# RPi_Motor_Driver_Rev_0_2.net
KiCad netlist of a schematic drawn in Altium Designer
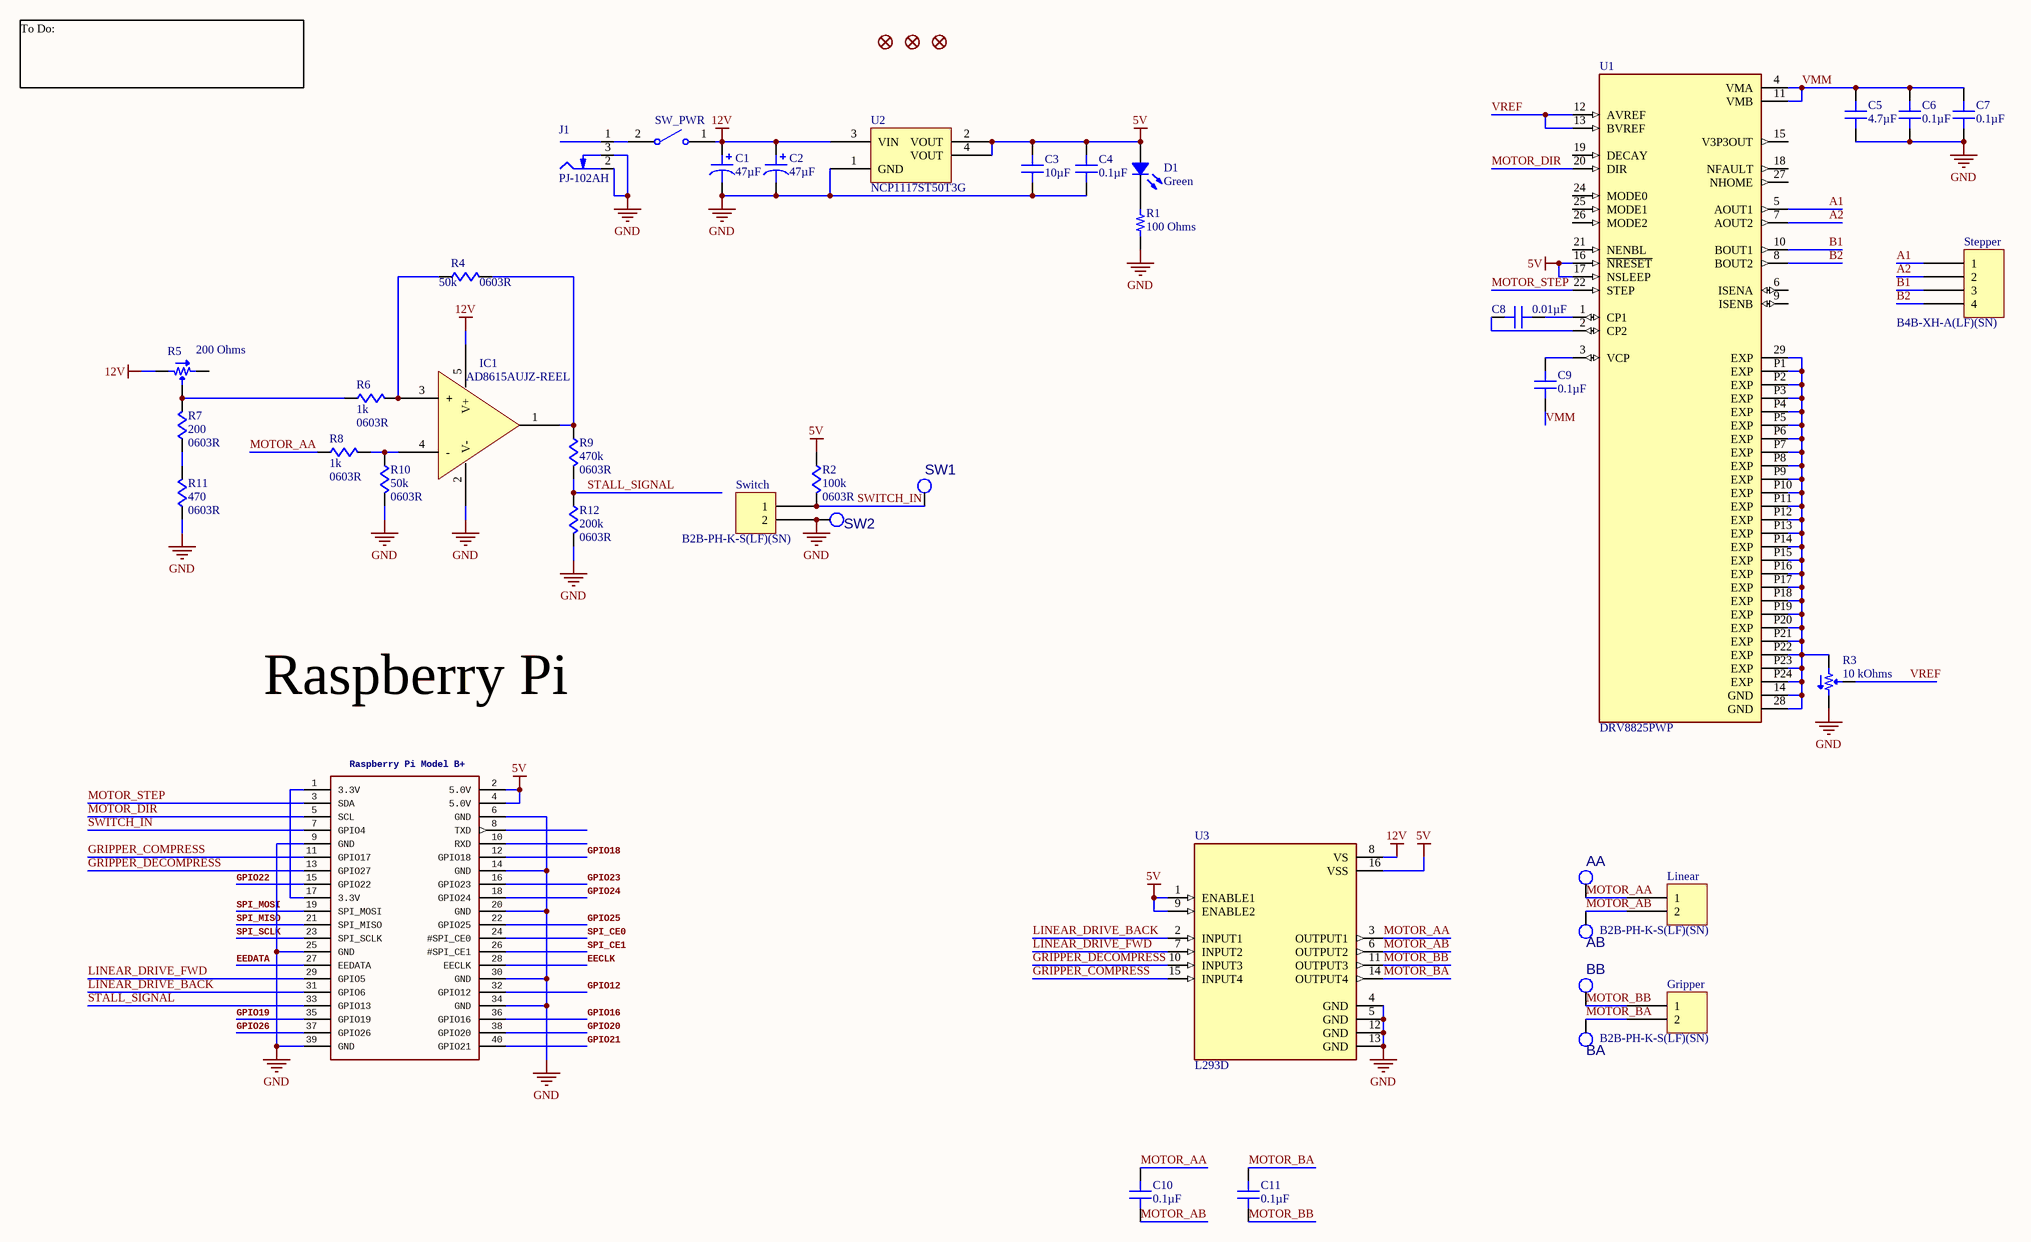
[diagram p0: RPi Motor Driver Rev 0.2.SchDoc]

(export (version "E")
  (design (tool "Eeschema 10.0.6"))
  (components
    (comp (ref "AA")
      (value "TH_Testpoint_40mil")
      (footprint "TH_Testpoint_40mil")
      (description "TH Testpoint")
      (libsource (lib "Testpoint") (part "TH_Testpoint_40mil"))
    )
    (comp (ref "AB")
      (value "TH_Testpoint_40mil")
      (footprint "TH_Testpoint_40mil")
      (description "TH Testpoint")
      (libsource (lib "Testpoint") (part "TH_Testpoint_40mil"))
    )
    (comp (ref "BA")
      (value "TH_Testpoint_40mil")
      (footprint "TH_Testpoint_40mil")
      (description "TH Testpoint")
      (libsource (lib "Testpoint") (part "TH_Testpoint_40mil"))
    )
    (comp (ref "BB")
      (value "TH_Testpoint_40mil")
      (footprint "TH_Testpoint_40mil")
      (description "TH Testpoint")
      (libsource (lib "Testpoint") (part "TH_Testpoint_40mil"))
    )
    (comp (ref "C1")
      (value "47µF")
      (footprint "CAP ALSMD 6.6MM H6.1MM")
      (description "CAP ALUM 47UF 20% 35V SMD")
      (fields (field (name "PART NUMBER") "EEE-FP1V470AP") (field (name "MANUFACTURER") "Nichicon"))
      (libsource (lib "Celestial Altium Library - altium_library") (part "Polarised Capacitor"))
    )
    (comp (ref "C2")
      (value "47µF")
      (footprint "CAP ALSMD 6.6MM H6.1MM")
      (description "CAP ALUM 47UF 20% 35V SMD")
      (fields (field (name "PART NUMBER") "EEE-FP1V470AP") (field (name "MANUFACTURER") "Nichicon"))
      (libsource (lib "Celestial Altium Library - altium_library") (part "Polarised Capacitor"))
    )
    (comp (ref "C3")
      (value "10µF")
      (footprint "CAP 0805_2012")
      (description "CAP CER 10UF 25V X5R 0805")
      (fields
        (field (name "PART NUMBER") "C2012X5R1E106K085AC")
        (field (name "MANUFACTURER") "TDK Corporation")
      )
      (libsource (lib "Celestial Altium Library - altium_library") (part "Capacitor"))
    )
    (comp (ref "C4")
      (value "0.1µF")
      (footprint "CAP 0603_1608")
      (description "CAP CER 0.1UF 50V X7R 0603")
      (fields
        (field (name "PART NUMBER") "CGA3E2X7R1H104K080AE")
        (field (name "MANUFACTURER") "TDK Corporation")
      )
      (libsource (lib "Celestial Altium Library - altium_library") (part "Capacitor"))
    )
    (comp (ref "C5")
      (value "4.7µF")
      (footprint "CAP 0603_1608")
      (description "CAP CER 4.7UF 35V X5R 0603")
      (fields
        (field (name "PART NUMBER") "C1608X5R1V475M080AC")
        (field (name "MANUFACTURER") "TDK Corporation")
      )
      (libsource (lib "Celestial Altium Library - altium_library") (part "Capacitor"))
    )
    (comp (ref "C6")
      (value "0.1µF")
      (footprint "CAP 0603_1608")
      (description "CAP CER 0.1UF 50V X7R 0603")
      (fields
        (field (name "PART NUMBER") "CGA3E2X7R1H104K080AE")
        (field (name "MANUFACTURER") "TDK Corporation")
      )
      (libsource (lib "Celestial Altium Library - altium_library") (part "Capacitor"))
    )
    (comp (ref "C7")
      (value "0.1µF")
      (footprint "CAP 0603_1608")
      (description "CAP CER 0.1UF 50V X7R 0603")
      (fields
        (field (name "PART NUMBER") "CGA3E2X7R1H104K080AE")
        (field (name "MANUFACTURER") "TDK Corporation")
      )
      (libsource (lib "Celestial Altium Library - altium_library") (part "Capacitor"))
    )
    (comp (ref "C8")
      (value "0.01µF")
      (footprint "CAP 0603_1608")
      (description "CAP CER 0.01UF 250V X7R 0603")
      (fields (field (name "PART NUMBER") "C0603C103KARACAUTO") (field (name "MANUFACTURER") "KEMET"))
      (libsource (lib "Celestial Altium Library - altium_library") (part "Capacitor"))
    )
    (comp (ref "C9")
      (value "0.1µF")
      (footprint "CAP 0603_1608")
      (description "CAP CER 0.1UF 50V X7R 0603")
      (fields
        (field (name "PART NUMBER") "CGA3E2X7R1H104K080AE")
        (field (name "MANUFACTURER") "TDK Corporation")
      )
      (libsource (lib "Celestial Altium Library - altium_library") (part "Capacitor"))
    )
    (comp (ref "C10")
      (value "0.1µF")
      (footprint "CAP 0603_1608")
      (description "CAP CER 0.1UF 50V X7R 0603")
      (fields
        (field (name "PART NUMBER") "CGA3E2X7R1H104K080AE")
        (field (name "MANUFACTURER") "TDK Corporation")
      )
      (libsource (lib "Celestial Altium Library - altium_library") (part "Capacitor"))
    )
    (comp (ref "C11")
      (value "0.1µF")
      (footprint "CAP 0603_1608")
      (description "CAP CER 0.1UF 50V X7R 0603")
      (fields
        (field (name "PART NUMBER") "CGA3E2X7R1H104K080AE")
        (field (name "MANUFACTURER") "TDK Corporation")
      )
      (libsource (lib "Celestial Altium Library - altium_library") (part "Capacitor"))
    )
    (comp (ref "D1")
      (value "Green")
      (footprint "LED 0603_1608 GREEN")
      (description "LED GREEN CLEAR 1608 SMD")
      (fields (field (name "PART NUMBER") "APT1608CGCK") (field (name "MANUFACTURER") "Kingbright"))
      (libsource (lib "Celestial Altium Library - altium_library") (part "LED"))
    )
    (comp (ref "FID1")
      (value "FIDUCIAL\"\"")
      (footprint "FIDUCIAL_1MM")
      (description "Fiducial Alignment PointsVarious fiducial points for machine vision alignment.")
      (libsource (lib "microbuilder") (part "FIDUCIAL{dblquote}{dblquote}"))
    )
    (comp (ref "FID2")
      (value "FIDUCIAL\"\"")
      (footprint "FIDUCIAL_1MM")
      (description "Fiducial Alignment PointsVarious fiducial points for machine vision alignment.")
      (libsource (lib "microbuilder") (part "FIDUCIAL{dblquote}{dblquote}"))
    )
    (comp (ref "FID3")
      (value "FIDUCIAL\"\"")
      (footprint "FIDUCIAL_1MM")
      (description "Fiducial Alignment PointsVarious fiducial points for machine vision alignment.")
      (libsource (lib "microbuilder") (part "FIDUCIAL{dblquote}{dblquote}"))
    )
    (comp (ref "Gripper")
      (value "B2B-PH-K-S(LF)(SN)")
      (footprint "JST B2B-PH-K")
      (description "CONN HEADER VERT 2POS 2MM")
      (fields (field (name "MANUFACTURER") "JST Sales America Inc."))
      (libsource (lib "") (part "2 Pin_1"))
    )
    (comp (ref "IC1")
      (value "AD8615AUJZ-REEL")
      (footprint "ANALOG TSOT-23-5 UJ-5")
      (description "IC OPAMP GP 1 CIRCUIT TSOT23-5")
      (fields (field (name "MANUFACTURER") "Analog Devices Inc."))
      (libsource (lib "Celestial Altium Library - altium_library") (part "ANALOG DEV AD8615AUJZ"))
    )
    (comp (ref "J1")
      (value "PJ-102AH")
      (footprint "CUI PJ-102AH")
      (description "CONN PWR JACK 2X5.5MM SOLDER")
      (fields (field (name "MANUFACTURER") "CUI Devices"))
      (libsource (lib "Celestial Altium Library - altium_library") (part "Barrel Connector"))
    )
    (comp (ref "Linear")
      (value "B2B-PH-K-S(LF)(SN)")
      (footprint "JST B2B-PH-K")
      (description "CONN HEADER VERT 2POS 2MM")
      (fields (field (name "MANUFACTURER") "JST Sales America Inc."))
      (libsource (lib "") (part "2 Pin_1"))
    )
    (comp (ref "R1")
      (value "100 Ohms")
      (footprint "RES 0603_1608")
      (description "RES 100 OHM 0.1% 1/16W 0603")
      (fields
        (field (name "PART NUMBER") "RNCS0603BKE100R")
        (field (name "MANUFACTURER") "Stackpole Electronics Inc")
      )
      (libsource (lib "Celestial Altium Library - altium_library") (part "Resistor"))
    )
    (comp (ref "R2")
      (value "100k")
      (footprint "0603R")
      (fields (field (name "Comment") "Resistor 0603"))
      (libsource (lib "MikesAltiumLibrary") (part "Resistor"))
    )
    (comp (ref "R3")
      (value "10 kOhms")
      (footprint "POT BOURNS TRIMPOT TC33")
      (description "TRIMMER 10K OHM 0.1W J LEAD TOP")
      (fields (field (name "PART NUMBER") "TC33X-2-103E") (field (name "MANUFACTURER") "Bourns Inc."))
      (libsource (lib "Celestial Altium Library - altium_library") (part "Potentiometer"))
    )
    (comp (ref "R4")
      (value "50k")
      (footprint "0603R")
      (fields (field (name "Comment") "Resistor 0603"))
      (libsource (lib "MikesAltiumLibrary") (part "Resistor"))
    )
    (comp (ref "R5")
      (value "200 Ohms")
      (footprint "POT BOURNS TRIMPOT TC33")
      (description "TRIMMER 200 OHM 0.1W J LEAD TOP")
      (fields (field (name "PART NUMBER") "TC33X-2-201E") (field (name "MANUFACTURER") "Bourns Inc."))
      (libsource (lib "Celestial Altium Library - altium_library") (part "Potentiometer"))
    )
    (comp (ref "R6")
      (value "1k")
      (footprint "0603R")
      (fields (field (name "Comment") "Resistor 0603"))
      (libsource (lib "MikesAltiumLibrary") (part "Resistor"))
    )
    (comp (ref "R7")
      (value "200")
      (footprint "0603R")
      (fields (field (name "Comment") "Resistor 0603"))
      (libsource (lib "MikesAltiumLibrary") (part "Resistor"))
    )
    (comp (ref "R8")
      (value "1k")
      (footprint "0603R")
      (fields (field (name "Comment") "Resistor 0603"))
      (libsource (lib "MikesAltiumLibrary") (part "Resistor"))
    )
    (comp (ref "R9")
      (value "470k")
      (footprint "0603R")
      (fields (field (name "Comment") "Resistor 0603"))
      (libsource (lib "MikesAltiumLibrary") (part "Resistor"))
    )
    (comp (ref "R10")
      (value "50k")
      (footprint "0603R")
      (fields (field (name "Comment") "Resistor 0603"))
      (libsource (lib "MikesAltiumLibrary") (part "Resistor"))
    )
    (comp (ref "R11")
      (value "470")
      (footprint "0603R")
      (fields (field (name "Comment") "Resistor 0603"))
      (libsource (lib "MikesAltiumLibrary") (part "Resistor"))
    )
    (comp (ref "R12")
      (value "200k")
      (footprint "0603R")
      (fields (field (name "Comment") "Resistor 0603"))
      (libsource (lib "MikesAltiumLibrary") (part "Resistor"))
    )
    (comp (ref "RPI1")
      (value "RASPBERRYPI_BPLUS_HATSLOTS")
      (footprint "PI_HAT_SLOTS")
      (fields (field (name "RASPBERRYPIMODELB+") "Raspberry Pi Model B+"))
      (libsource (lib "microbuilder") (part "RASPBERRYPI_BPLUS_HATSLOTS"))
    )
    (comp (ref "Stepper")
      (value "B4B-XH-A(LF)(SN)")
      (footprint "JST XH B4B-XH-A")
      (description "CONN HEADER VERT 4POS 2.5MM")
      (fields (field (name "MANUFACTURER") "JST Sales America Inc."))
      (libsource (lib "Celestial Altium Library - altium_library") (part "4 Pin"))
    )
    (comp (ref "SW1")
      (value "TH_Testpoint_40mil")
      (footprint "TH_Testpoint_40mil")
      (description "TH Testpoint")
      (libsource (lib "Testpoint") (part "TH_Testpoint_40mil"))
    )
    (comp (ref "SW2")
      (value "TH_Testpoint_40mil")
      (footprint "TH_Testpoint_40mil")
      (description "TH Testpoint")
      (libsource (lib "Testpoint") (part "TH_Testpoint_40mil"))
    )
    (comp (ref "Switch")
      (value "B2B-PH-K-S(LF)(SN)")
      (footprint "JST B2B-PH-K")
      (description "CONN HEADER VERT 2POS 2MM")
      (fields (field (name "MANUFACTURER") "JST Sales America Inc."))
      (libsource (lib "Celestial Altium Library - altium_library") (part "2 Pin"))
    )
    (comp (ref "SW_PWR")
      (value "48ASSP3S1M2QBT")
      (footprint "SWITCH SLIDE SPDT 5A 125V")
      (description "SWITCH SLIDE SPDT 5A 125V")
      (libsource (lib "MikesAltiumLibrary") (part "SWITCH SLIDE SPDT 5A 125V"))
    )
    (comp (ref "U1")
      (value "DRV8825PWP")
      (footprint "SOP65P640X120-29N")
      (description "Bipolar Motor Driver Power MOSFET Logic 28-HTSSOP")
      (fields (field (name "MF") "Texas Instruments"))
      (libsource (lib "MikesAltiumLibrary") (part "DRV8825PWP"))
    )
    (comp (ref "U2")
      (value "NCP1117ST50T3G")
      (footprint "ON SEMI SOT-223 ST(318H)")
      (description "IC REG LINEAR 5V 1A SOT223")
      (fields (field (name "MANUFACTURER") "ON Semiconductor"))
      (libsource (lib "Celestial Altium Library - altium_library") (part "ON Semi NCP1117"))
    )
    (comp (ref "U3")
      (value "L293D")
      (footprint "DIP880W50P254L2000H510Q16")
      (description "Bipolar Motor Driver Parallel 16-PowerDIP")
      (fields (field (name "MF") "STMicroelectronics"))
      (libsource (lib "MikesAltiumLibrary") (part "L293D"))
    )
  )
  (nets
    (net (code "1") (name "/A1") (class "Default")
      (node (ref "Stepper") (pin "1") (pinfunction "1_1") (pintype "passive"))
      (node (ref "U1") (pin "5") (pinfunction "AOUT1_5") (pintype "output"))
    )
    (net (code "2") (name "/A2") (class "Default")
      (node (ref "Stepper") (pin "2") (pinfunction "2_2") (pintype "passive"))
      (node (ref "U1") (pin "7") (pinfunction "AOUT2_7") (pintype "output"))
    )
    (net (code "3") (name "/B1") (class "Default")
      (node (ref "Stepper") (pin "3") (pinfunction "3_3") (pintype "passive"))
      (node (ref "U1") (pin "10") (pinfunction "BOUT1_10") (pintype "output"))
    )
    (net (code "4") (name "/B2") (class "Default")
      (node (ref "Stepper") (pin "4") (pinfunction "4_4") (pintype "passive"))
      (node (ref "U1") (pin "8") (pinfunction "BOUT2_8") (pintype "output"))
    )
    (net (code "5") (name "/EECLK") (class "Default")
      (node (ref "RPI1") (pin "28") (pinfunction "EECLK_28") (pintype "open_emitter"))
    )
    (net (code "6") (name "/EEDATA") (class "Default")
      (node (ref "RPI1") (pin "27") (pinfunction "EEDATA_27") (pintype "passive"))
    )
    (net (code "7") (name "/GPIO12") (class "Default")
      (node (ref "RPI1") (pin "32") (pinfunction "GPIO12_32") (pintype "passive"))
    )
    (net (code "8") (name "/GPIO16") (class "Default")
      (node (ref "RPI1") (pin "36") (pinfunction "GPIO16_36") (pintype "open_emitter"))
    )
    (net (code "9") (name "/GPIO18") (class "Default")
      (node (ref "RPI1") (pin "12") (pinfunction "GPIO18_12") (pintype "passive"))
    )
    (net (code "10") (name "/GPIO19") (class "Default")
      (node (ref "RPI1") (pin "35") (pinfunction "GPIO19_35") (pintype "passive"))
    )
    (net (code "11") (name "/GPIO20") (class "Default")
      (node (ref "RPI1") (pin "38") (pinfunction "GPIO20_38") (pintype "passive"))
    )
    (net (code "12") (name "/GPIO21") (class "Default")
      (node (ref "RPI1") (pin "40") (pinfunction "GPIO21_40") (pintype "passive"))
    )
    (net (code "13") (name "/GPIO22") (class "Default")
      (node (ref "RPI1") (pin "15") (pinfunction "GPIO22_15") (pintype "passive"))
    )
    (net (code "14") (name "/GPIO23") (class "Default")
      (node (ref "RPI1") (pin "16") (pinfunction "GPIO23_16") (pintype "passive"))
    )
    (net (code "15") (name "/GPIO24") (class "Default")
      (node (ref "RPI1") (pin "18") (pinfunction "GPIO24_18") (pintype "passive"))
    )
    (net (code "16") (name "/GPIO25") (class "Default")
      (node (ref "RPI1") (pin "22") (pinfunction "GPIO25_22") (pintype "passive"))
    )
    (net (code "17") (name "/GPIO26") (class "Default")
      (node (ref "RPI1") (pin "37") (pinfunction "GPIO26_37") (pintype "passive"))
    )
    (net (code "18") (name "/GRIPPER_COMPRESS") (class "Default")
      (node (ref "RPI1") (pin "11") (pinfunction "GPIO17_11") (pintype "passive"))
      (node (ref "U3") (pin "15") (pinfunction "INPUT4_15") (pintype "input"))
    )
    (net (code "19") (name "/GRIPPER_DECOMPRESS") (class "Default")
      (node (ref "RPI1") (pin "13") (pinfunction "GPIO27_13") (pintype "passive"))
      (node (ref "U3") (pin "10") (pinfunction "INPUT3_10") (pintype "input"))
    )
    (net (code "20") (name "/LINEAR_DRIVE_BACK") (class "Default")
      (node (ref "RPI1") (pin "31") (pinfunction "GPIO6_31") (pintype "open_emitter"))
      (node (ref "U3") (pin "2") (pinfunction "INPUT1_2") (pintype "input"))
    )
    (net (code "21") (name "/LINEAR_DRIVE_FWD") (class "Default")
      (node (ref "RPI1") (pin "29") (pinfunction "GPIO5_29") (pintype "passive"))
      (node (ref "U3") (pin "7") (pinfunction "INPUT2_7") (pintype "input"))
    )
    (net (code "22") (name "/MOTOR_AA") (class "Default")
      (node (ref "AA") (pin "1") (pinfunction "1_1") (pintype "passive"))
      (node (ref "C10") (pin "2") (pinfunction "2_2") (pintype "passive"))
      (node (ref "Linear") (pin "1") (pinfunction "1_1") (pintype "passive"))
      (node (ref "R8") (pin "2") (pinfunction "2_2") (pintype "power_in"))
      (node (ref "U3") (pin "3") (pinfunction "OUTPUT1_3") (pintype "output"))
    )
    (net (code "23") (name "/MOTOR_AB") (class "Default")
      (node (ref "AB") (pin "1") (pinfunction "1_1") (pintype "passive"))
      (node (ref "C10") (pin "1") (pinfunction "1_1") (pintype "passive"))
      (node (ref "Linear") (pin "2") (pinfunction "2_2") (pintype "passive"))
      (node (ref "U3") (pin "6") (pinfunction "OUTPUT2_6") (pintype "output"))
    )
    (net (code "24") (name "/MOTOR_BA") (class "Default")
      (node (ref "BA") (pin "1") (pinfunction "1_1") (pintype "passive"))
      (node (ref "C11") (pin "2") (pinfunction "2_2") (pintype "passive"))
      (node (ref "Gripper") (pin "2") (pinfunction "2_2") (pintype "passive"))
      (node (ref "U3") (pin "14") (pinfunction "OUTPUT4_14") (pintype "output"))
    )
    (net (code "25") (name "/MOTOR_BB") (class "Default")
      (node (ref "BB") (pin "1") (pinfunction "1_1") (pintype "passive"))
      (node (ref "C11") (pin "1") (pinfunction "1_1") (pintype "passive"))
      (node (ref "Gripper") (pin "1") (pinfunction "1_1") (pintype "passive"))
      (node (ref "U3") (pin "11") (pinfunction "OUTPUT3_11") (pintype "output"))
    )
    (net (code "26") (name "/MOTOR_DIR") (class "Default")
      (node (ref "RPI1") (pin "5") (pinfunction "SCL_5") (pintype "passive"))
      (node (ref "U1") (pin "20") (pinfunction "DIR_20") (pintype "input"))
    )
    (net (code "27") (name "/MOTOR_STEP") (class "Default")
      (node (ref "RPI1") (pin "3") (pinfunction "SDA_3") (pintype "passive"))
      (node (ref "U1") (pin "22") (pinfunction "STEP_22") (pintype "input"))
    )
    (net (code "28") (name "/SPI_CE0") (class "Default")
      (node (ref "RPI1") (pin "24") (pinfunction "#SPI_CE0_24") (pintype "passive"))
    )
    (net (code "29") (name "/SPI_CE1") (class "Default")
      (node (ref "RPI1") (pin "26") (pinfunction "#SPI_CE1_26") (pintype "passive"))
    )
    (net (code "30") (name "/SPI_MISO") (class "Default")
      (node (ref "RPI1") (pin "21") (pinfunction "SPI_MISO_21") (pintype "passive"))
    )
    (net (code "31") (name "/SPI_MOSI") (class "Default")
      (node (ref "RPI1") (pin "19") (pinfunction "SPI_MOSI_19") (pintype "passive"))
    )
    (net (code "32") (name "/SPI_SCLK") (class "Default")
      (node (ref "RPI1") (pin "23") (pinfunction "SPI_SCLK_23") (pintype "passive"))
    )
    (net (code "33") (name "/STALL_SIGNAL") (class "Default")
      (node (ref "R12") (pin "2") (pinfunction "2_2") (pintype "power_in"))
      (node (ref "R9") (pin "1") (pinfunction "1_1") (pintype "power_in"))
      (node (ref "RPI1") (pin "33") (pinfunction "GPIO13_33") (pintype "passive"))
    )
    (net (code "34") (name "/SWITCH_IN") (class "Default")
      (node (ref "R2") (pin "1") (pinfunction "1_1") (pintype "power_in"))
      (node (ref "RPI1") (pin "7") (pinfunction "GPIO4_7") (pintype "passive"))
      (node (ref "SW1") (pin "1") (pinfunction "1_1") (pintype "passive"))
      (node (ref "Switch") (pin "1") (pinfunction "1_1") (pintype "passive"))
    )
    (net (code "35") (name "/VMM") (class "Default")
      (node (ref "C5") (pin "2") (pinfunction "2_2") (pintype "passive"))
      (node (ref "C6") (pin "2") (pinfunction "2_2") (pintype "passive"))
      (node (ref "C7") (pin "2") (pinfunction "2_2") (pintype "passive"))
      (node (ref "C9") (pin "1") (pinfunction "1_1") (pintype "passive"))
      (node (ref "U1") (pin "11") (pinfunction "VMB_11") (pintype "power_in"))
      (node (ref "U1") (pin "4") (pinfunction "VMA_4") (pintype "power_in"))
    )
    (net (code "36") (name "/VREF") (class "Default")
      (node (ref "R3") (pin "2") (pinfunction "2_2") (pintype "passive"))
      (node (ref "U1") (pin "12") (pinfunction "AVREF_12") (pintype "input"))
      (node (ref "U1") (pin "13") (pinfunction "BVREF_13") (pintype "input"))
    )
    (net (code "37") (name "5V") (class "Default")
      (node (ref "C3") (pin "2") (pinfunction "2_2") (pintype "passive"))
      (node (ref "C4") (pin "2") (pinfunction "2_2") (pintype "passive"))
      (node (ref "D1") (pin "1") (pinfunction "1_1") (pintype "passive"))
      (node (ref "R2") (pin "2") (pinfunction "2_2") (pintype "power_in"))
      (node (ref "RPI1") (pin "2") (pinfunction "5.0V_2") (pintype "open_emitter"))
      (node (ref "RPI1") (pin "4") (pinfunction "5.0V_4") (pintype "open_emitter"))
      (node (ref "U1") (pin "16") (pinfunction "~{NRESET}_16") (pintype "input"))
      (node (ref "U1") (pin "17") (pinfunction "NSLEEP_17") (pintype "input"))
      (node (ref "U2") (pin "2") (pinfunction "VOUT_2") (pintype "passive"))
      (node (ref "U2") (pin "4") (pinfunction "VOUT_4") (pintype "passive"))
      (node (ref "U3") (pin "1") (pinfunction "ENABLE1_1") (pintype "input"))
      (node (ref "U3") (pin "16") (pinfunction "VSS_16") (pintype "power_in"))
      (node (ref "U3") (pin "9") (pinfunction "ENABLE2_9") (pintype "input"))
    )
    (net (code "38") (name "12V") (class "Default")
      (node (ref "C1") (pin "1") (pinfunction "1_1") (pintype "passive"))
      (node (ref "C2") (pin "1") (pinfunction "1_1") (pintype "passive"))
      (node (ref "IC1") (pin "5") (pinfunction "V+_5") (pintype "passive"))
      (node (ref "R5") (pin "1") (pinfunction "1_1") (pintype "passive"))
      (node (ref "SW_PWR") (pin "1") (pinfunction "1_1") (pintype "passive"))
      (node (ref "U2") (pin "3") (pinfunction "VIN_3") (pintype "passive"))
      (node (ref "U3") (pin "8") (pinfunction "VS_8") (pintype "power_in"))
    )
    (net (code "39") (name "GND") (class "Default")
      (node (ref "C1") (pin "2") (pinfunction "2_2") (pintype "passive"))
      (node (ref "C2") (pin "2") (pinfunction "2_2") (pintype "passive"))
      (node (ref "C3") (pin "1") (pinfunction "1_1") (pintype "passive"))
      (node (ref "C4") (pin "1") (pinfunction "1_1") (pintype "passive"))
      (node (ref "C5") (pin "1") (pinfunction "1_1") (pintype "passive"))
      (node (ref "C6") (pin "1") (pinfunction "1_1") (pintype "passive"))
      (node (ref "C7") (pin "1") (pinfunction "1_1") (pintype "passive"))
      (node (ref "IC1") (pin "2") (pinfunction "V-_2") (pintype "passive"))
      (node (ref "J1") (pin "2") (pinfunction "Outer_2") (pintype "passive"))
      (node (ref "J1") (pin "3") (pinfunction "SW_3") (pintype "passive"))
      (node (ref "R1") (pin "1") (pinfunction "1_1") (pintype "passive"))
      (node (ref "R10") (pin "1") (pinfunction "1_1") (pintype "power_in"))
      (node (ref "R11") (pin "2") (pinfunction "2_2") (pintype "power_in"))
      (node (ref "R12") (pin "1") (pinfunction "1_1") (pintype "power_in"))
      (node (ref "R3") (pin "3") (pinfunction "3_3") (pintype "passive"))
      (node (ref "RPI1") (pin "14") (pinfunction "GND_14") (pintype "open_emitter"))
      (node (ref "RPI1") (pin "20") (pinfunction "GND_20") (pintype "open_emitter"))
      (node (ref "RPI1") (pin "25") (pinfunction "GND_25") (pintype "open_emitter"))
      (node (ref "RPI1") (pin "30") (pinfunction "GND_30") (pintype "passive"))
      (node (ref "RPI1") (pin "34") (pinfunction "GND_34") (pintype "passive"))
      (node (ref "RPI1") (pin "39") (pinfunction "GND_39") (pintype "open_emitter"))
      (node (ref "RPI1") (pin "6") (pinfunction "GND_6") (pintype "open_emitter"))
      (node (ref "RPI1") (pin "9") (pinfunction "GND_9") (pintype "open_emitter"))
      (node (ref "SW2") (pin "1") (pinfunction "1_1") (pintype "passive"))
      (node (ref "Switch") (pin "2") (pinfunction "2_2") (pintype "passive"))
      (node (ref "U2") (pin "1") (pinfunction "GND_1") (pintype "passive"))
      (node (ref "U3") (pin "12") (pinfunction "GND_12") (pintype "power_in"))
      (node (ref "U3") (pin "13") (pinfunction "GND_13") (pintype "power_in"))
      (node (ref "U3") (pin "4") (pinfunction "GND_4") (pintype "power_in"))
      (node (ref "U3") (pin "5") (pinfunction "GND_5") (pintype "power_in"))
    )
    (net (code "40") (name "Net-(D1-Pad2)") (class "Default")
      (node (ref "D1") (pin "2") (pinfunction "2_2") (pintype "passive"))
      (node (ref "R1") (pin "2") (pinfunction "2_2") (pintype "passive"))
    )
    (net (code "41") (name "Net-(IC1-+)") (class "Default")
      (node (ref "IC1") (pin "3") (pinfunction "+_3") (pintype "passive"))
      (node (ref "R4") (pin "2") (pinfunction "2_2") (pintype "power_in"))
      (node (ref "R6") (pin "1") (pinfunction "1_1") (pintype "power_in"))
    )
    (net (code "42") (name "Net-(IC1--)") (class "Default")
      (node (ref "IC1") (pin "4") (pinfunction "-_4") (pintype "passive"))
      (node (ref "R10") (pin "2") (pinfunction "2_2") (pintype "power_in"))
      (node (ref "R8") (pin "1") (pinfunction "1_1") (pintype "power_in"))
    )
    (net (code "43") (name "Net-(IC1-OUT)") (class "Default")
      (node (ref "IC1") (pin "1") (pinfunction "OUT_1") (pintype "passive"))
      (node (ref "R4") (pin "1") (pinfunction "1_1") (pintype "power_in"))
      (node (ref "R9") (pin "2") (pinfunction "2_2") (pintype "power_in"))
    )
    (net (code "44") (name "Net-(J1-Centre)") (class "Default")
      (node (ref "J1") (pin "1") (pinfunction "Centre_1") (pintype "passive"))
      (node (ref "SW_PWR") (pin "2") (pinfunction "2_2") (pintype "passive"))
    )
    (net (code "45") (name "Net-(R3-Pad1)") (class "Default")
      (node (ref "R3") (pin "1") (pinfunction "1_1") (pintype "passive"))
      (node (ref "U1") (pin "14") (pinfunction "GND_14") (pintype "power_in"))
      (node (ref "U1") (pin "28") (pinfunction "GND_28") (pintype "power_in"))
      (node (ref "U1") (pin "29") (pinfunction "EXP_29") (pintype "power_in"))
      (node (ref "U1") (pin "P1") (pinfunction "EXP_P1") (pintype "power_in"))
      (node (ref "U1") (pin "P10") (pinfunction "EXP_P10") (pintype "power_in"))
      (node (ref "U1") (pin "P11") (pinfunction "EXP_P11") (pintype "power_in"))
      (node (ref "U1") (pin "P12") (pinfunction "EXP_P12") (pintype "power_in"))
      (node (ref "U1") (pin "P13") (pinfunction "EXP_P13") (pintype "power_in"))
      (node (ref "U1") (pin "P14") (pinfunction "EXP_P14") (pintype "power_in"))
      (node (ref "U1") (pin "P15") (pinfunction "EXP_P15") (pintype "power_in"))
      (node (ref "U1") (pin "P16") (pinfunction "EXP_P16") (pintype "power_in"))
      (node (ref "U1") (pin "P17") (pinfunction "EXP_P17") (pintype "power_in"))
      (node (ref "U1") (pin "P18") (pinfunction "EXP_P18") (pintype "power_in"))
      (node (ref "U1") (pin "P19") (pinfunction "EXP_P19") (pintype "power_in"))
      (node (ref "U1") (pin "P2") (pinfunction "EXP_P2") (pintype "power_in"))
      (node (ref "U1") (pin "P20") (pinfunction "EXP_P20") (pintype "power_in"))
      (node (ref "U1") (pin "P21") (pinfunction "EXP_P21") (pintype "power_in"))
      (node (ref "U1") (pin "P22") (pinfunction "EXP_P22") (pintype "power_in"))
      (node (ref "U1") (pin "P23") (pinfunction "EXP_P23") (pintype "power_in"))
      (node (ref "U1") (pin "P24") (pinfunction "EXP_P24") (pintype "power_in"))
      (node (ref "U1") (pin "P3") (pinfunction "EXP_P3") (pintype "power_in"))
      (node (ref "U1") (pin "P4") (pinfunction "EXP_P4") (pintype "power_in"))
      (node (ref "U1") (pin "P5") (pinfunction "EXP_P5") (pintype "power_in"))
      (node (ref "U1") (pin "P6") (pinfunction "EXP_P6") (pintype "power_in"))
      (node (ref "U1") (pin "P7") (pinfunction "EXP_P7") (pintype "power_in"))
      (node (ref "U1") (pin "P8") (pinfunction "EXP_P8") (pintype "power_in"))
      (node (ref "U1") (pin "P9") (pinfunction "EXP_P9") (pintype "power_in"))
    )
    (net (code "46") (name "Net-(R5-Pad2)") (class "Default")
      (node (ref "R5") (pin "2") (pinfunction "2_2") (pintype "passive"))
      (node (ref "R6") (pin "2") (pinfunction "2_2") (pintype "power_in"))
      (node (ref "R7") (pin "1") (pinfunction "1_1") (pintype "power_in"))
    )
    (net (code "47") (name "Net-(R11-Pad1)") (class "Default")
      (node (ref "R11") (pin "1") (pinfunction "1_1") (pintype "power_in"))
      (node (ref "R7") (pin "2") (pinfunction "2_2") (pintype "power_in"))
    )
    (net (code "48") (name "Net-(RPI1-3.3V-Pad1)") (class "Default")
      (node (ref "RPI1") (pin "1") (pinfunction "3.3V_1") (pintype "open_emitter"))
      (node (ref "RPI1") (pin "17") (pinfunction "3.3V_17") (pintype "open_emitter"))
    )
    (net (code "49") (name "Net-(U1-CP1)") (class "Default")
      (node (ref "C8") (pin "2") (pinfunction "2_2") (pintype "passive"))
      (node (ref "U1") (pin "1") (pinfunction "CP1_1") (pintype "bidirectional"))
    )
    (net (code "50") (name "Net-(U1-CP2)") (class "Default")
      (node (ref "C8") (pin "1") (pinfunction "1_1") (pintype "passive"))
      (node (ref "U1") (pin "2") (pinfunction "CP2_2") (pintype "bidirectional"))
    )
    (net (code "51") (name "Net-(U1-VCP)") (class "Default")
      (node (ref "C9") (pin "2") (pinfunction "2_2") (pintype "passive"))
      (node (ref "U1") (pin "3") (pinfunction "VCP_3") (pintype "bidirectional"))
    )
    (net (code "52") (name "unconnected-(R5-Pad3)") (class "Default")
      (node (ref "R5") (pin "3") (pinfunction "3_3") (pintype "passive"))
    )
    (net (code "53") (name "unconnected-(RPI1-RXD-Pad10)") (class "Default")
      (node (ref "RPI1") (pin "10") (pinfunction "RXD_10") (pintype "passive"))
    )
    (net (code "54") (name "unconnected-(RPI1-TXD-Pad8)") (class "Default")
      (node (ref "RPI1") (pin "8") (pinfunction "TXD_8") (pintype "output"))
    )
    (net (code "55") (name "unconnected-(U1-DECAY-Pad19)") (class "Default")
      (node (ref "U1") (pin "19") (pinfunction "DECAY_19") (pintype "input"))
    )
    (net (code "56") (name "unconnected-(U1-ISENA-Pad6)") (class "Default")
      (node (ref "U1") (pin "6") (pinfunction "ISENA_6") (pintype "bidirectional"))
    )
    (net (code "57") (name "unconnected-(U1-ISENB-Pad9)") (class "Default")
      (node (ref "U1") (pin "9") (pinfunction "ISENB_9") (pintype "bidirectional"))
    )
    (net (code "58") (name "unconnected-(U1-MODE0-Pad24)") (class "Default")
      (node (ref "U1") (pin "24") (pinfunction "MODE0_24") (pintype "input"))
    )
    (net (code "59") (name "unconnected-(U1-MODE1-Pad25)") (class "Default")
      (node (ref "U1") (pin "25") (pinfunction "MODE1_25") (pintype "input"))
    )
    (net (code "60") (name "unconnected-(U1-MODE2-Pad26)") (class "Default")
      (node (ref "U1") (pin "26") (pinfunction "MODE2_26") (pintype "input"))
    )
    (net (code "61") (name "unconnected-(U1-NENBL-Pad21)") (class "Default")
      (node (ref "U1") (pin "21") (pinfunction "NENBL_21") (pintype "input"))
    )
    (net (code "62") (name "unconnected-(U1-NFAULT-Pad18)") (class "Default")
      (node (ref "U1") (pin "18") (pinfunction "NFAULT_18") (pintype "output"))
    )
    (net (code "63") (name "unconnected-(U1-NHOME-Pad27)") (class "Default")
      (node (ref "U1") (pin "27") (pinfunction "NHOME_27") (pintype "output"))
    )
    (net (code "64") (name "unconnected-(U1-V3P3OUT-Pad15)") (class "Default")
      (node (ref "U1") (pin "15") (pinfunction "V3P3OUT_15") (pintype "output"))
    )
  )
)
